# dip.net
KiCad netlist of a schematic drawn in EAGLE
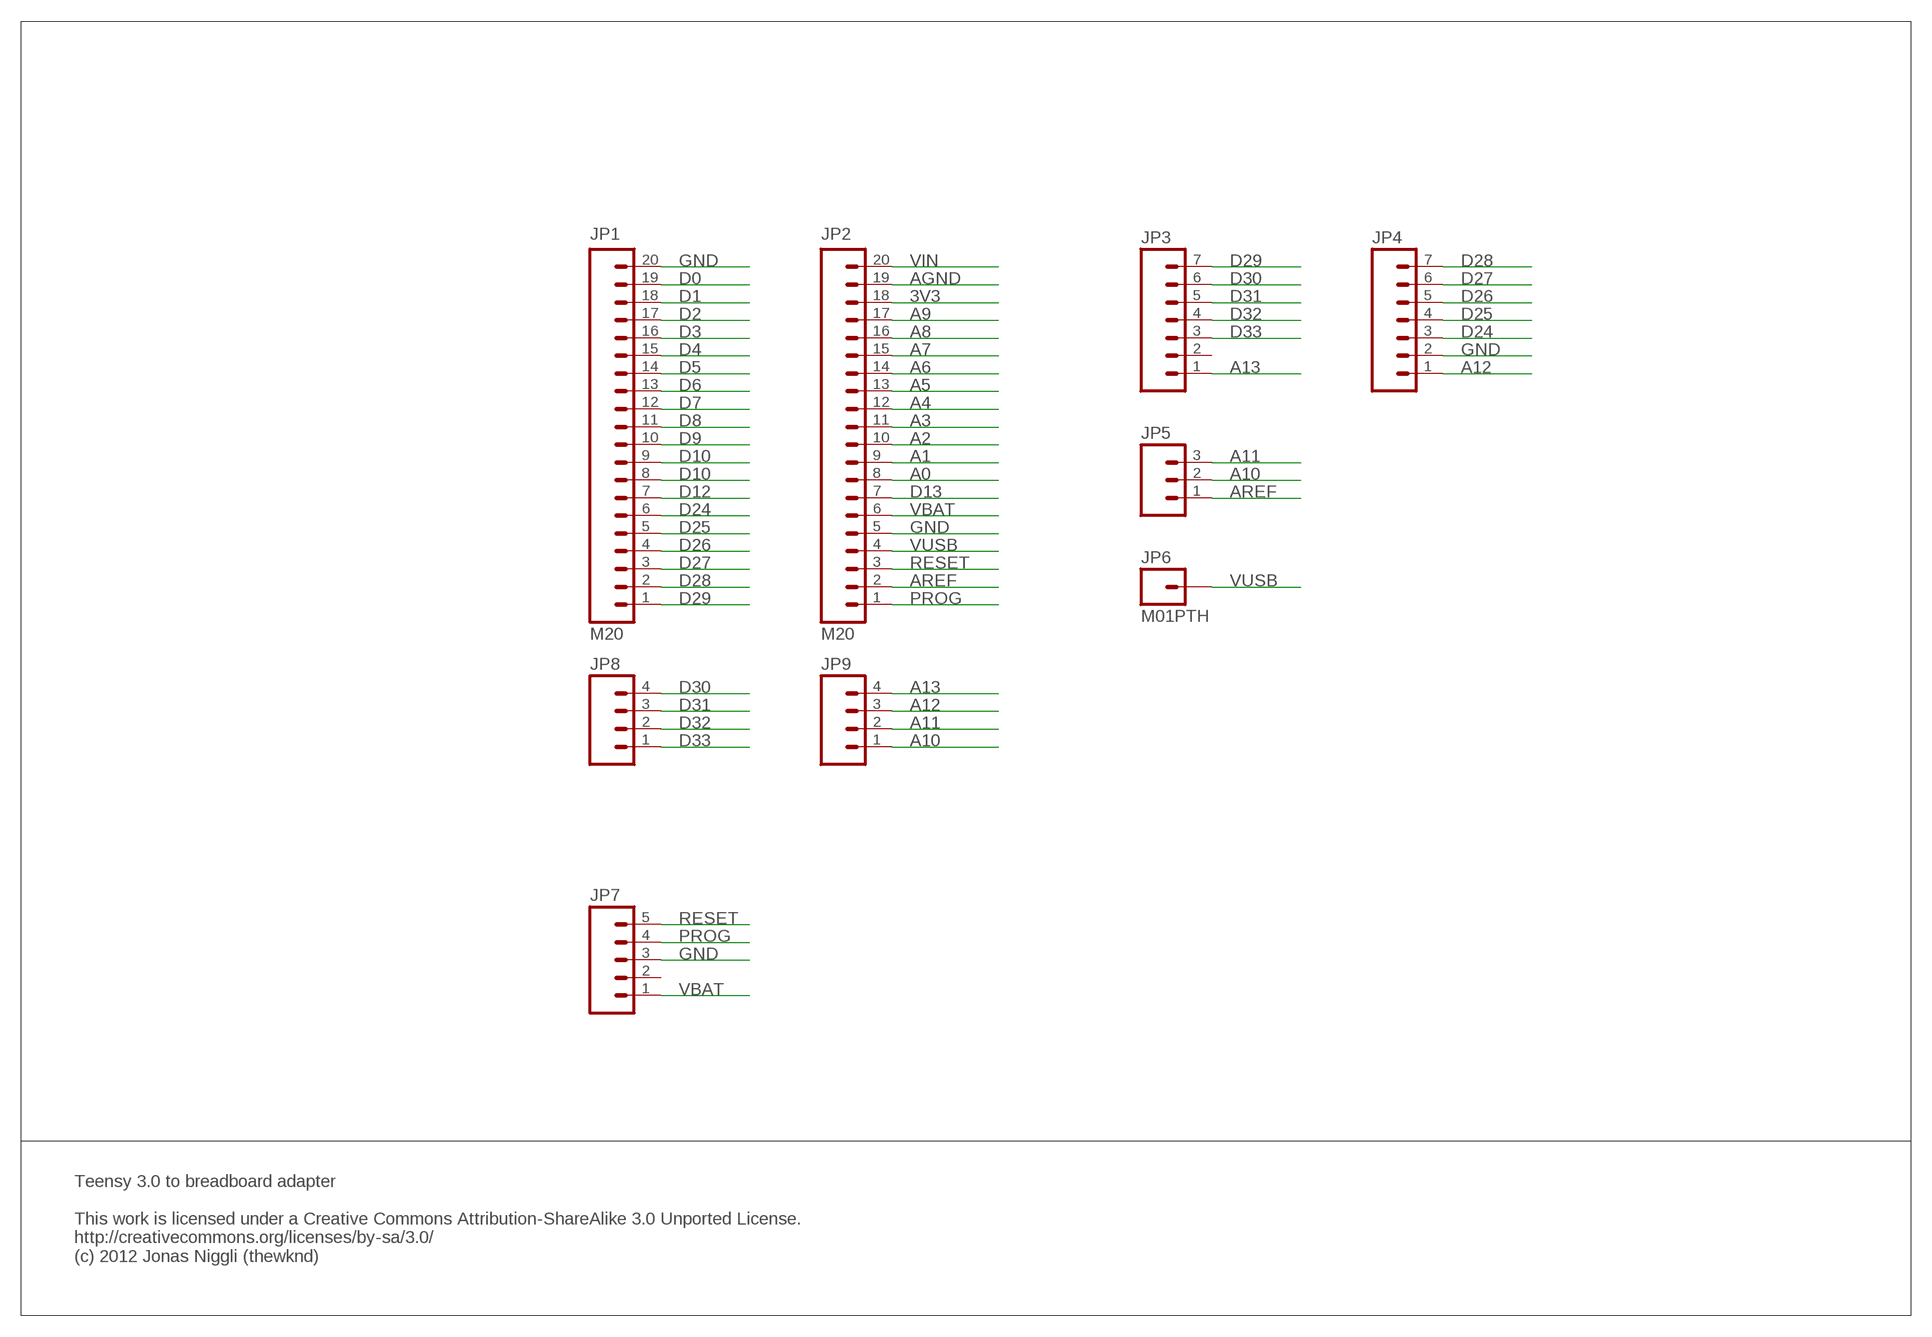
[diagram p0: schematic, sheet 1]

(export (version "E")
  (design (tool "Eeschema 10.0.6"))
  (components
    (comp (ref "JP1")
      (value "M20")
      (footprint "eagle-import:1X20")
      (libsource (lib "eagle-import") (part "M20"))
    )
    (comp (ref "JP2")
      (value "M20")
      (footprint "eagle-import:1X20")
      (libsource (lib "eagle-import") (part "M20"))
    )
    (comp (ref "JP3")
      (value "M07")
      (footprint "eagle-import:1X07")
      (libsource (lib "eagle-import") (part "M07"))
    )
    (comp (ref "JP4")
      (value "M07")
      (footprint "eagle-import:1X07")
      (libsource (lib "eagle-import") (part "M07"))
    )
    (comp (ref "JP5")
      (value "M03PTH")
      (footprint "eagle-import:1X03")
      (libsource (lib "eagle-import") (part "M03PTH"))
    )
    (comp (ref "JP6")
      (value "M01PTH")
      (footprint "eagle-import:1X01")
      (libsource (lib "eagle-import") (part "M01PTH"))
    )
    (comp (ref "JP7")
      (value "M05PTH")
      (footprint "eagle-import:1X05")
      (libsource (lib "eagle-import") (part "M05PTH"))
    )
    (comp (ref "JP8")
      (value "M04PTH")
      (footprint "eagle-import:1X04")
      (libsource (lib "eagle-import") (part "M04PTH"))
    )
    (comp (ref "JP9")
      (value "M04PTH")
      (footprint "eagle-import:1X04")
      (libsource (lib "eagle-import") (part "M04PTH"))
    )
  )
  (nets
    (net (code "1") (name "/3V3") (class "Default")
      (node (ref "JP2") (pin "18") (pinfunction "18_18") (pintype "passive"))
    )
    (net (code "2") (name "/A0") (class "Default")
      (node (ref "JP2") (pin "8") (pinfunction "8_8") (pintype "passive"))
    )
    (net (code "3") (name "/A1") (class "Default")
      (node (ref "JP2") (pin "9") (pinfunction "9_9") (pintype "passive"))
    )
    (net (code "4") (name "/A2") (class "Default")
      (node (ref "JP2") (pin "10") (pinfunction "10_10") (pintype "passive"))
    )
    (net (code "5") (name "/A3") (class "Default")
      (node (ref "JP2") (pin "11") (pinfunction "11_11") (pintype "passive"))
    )
    (net (code "6") (name "/A4") (class "Default")
      (node (ref "JP2") (pin "12") (pinfunction "12_12") (pintype "passive"))
    )
    (net (code "7") (name "/A5") (class "Default")
      (node (ref "JP2") (pin "13") (pinfunction "13_13") (pintype "passive"))
    )
    (net (code "8") (name "/A6") (class "Default")
      (node (ref "JP2") (pin "14") (pinfunction "14_14") (pintype "passive"))
    )
    (net (code "9") (name "/A7") (class "Default")
      (node (ref "JP2") (pin "15") (pinfunction "15_15") (pintype "passive"))
    )
    (net (code "10") (name "/A8") (class "Default")
      (node (ref "JP2") (pin "16") (pinfunction "16_16") (pintype "passive"))
    )
    (net (code "11") (name "/A9") (class "Default")
      (node (ref "JP2") (pin "17") (pinfunction "17_17") (pintype "passive"))
    )
    (net (code "12") (name "/A10") (class "Default")
      (node (ref "JP5") (pin "2") (pinfunction "2_2") (pintype "passive"))
      (node (ref "JP9") (pin "1") (pinfunction "1_1") (pintype "passive"))
    )
    (net (code "13") (name "/A11") (class "Default")
      (node (ref "JP5") (pin "3") (pinfunction "3_3") (pintype "passive"))
      (node (ref "JP9") (pin "2") (pinfunction "2_2") (pintype "passive"))
    )
    (net (code "14") (name "/A12") (class "Default")
      (node (ref "JP4") (pin "1") (pinfunction "1_1") (pintype "passive"))
      (node (ref "JP9") (pin "3") (pinfunction "3_3") (pintype "passive"))
    )
    (net (code "15") (name "/A13") (class "Default")
      (node (ref "JP3") (pin "1") (pinfunction "1_1") (pintype "passive"))
      (node (ref "JP9") (pin "4") (pinfunction "4_4") (pintype "passive"))
    )
    (net (code "16") (name "/AGND") (class "Default")
      (node (ref "JP2") (pin "19") (pinfunction "19_19") (pintype "passive"))
    )
    (net (code "17") (name "/AREF") (class "Default")
      (node (ref "JP2") (pin "2") (pinfunction "2_2") (pintype "passive"))
      (node (ref "JP5") (pin "1") (pinfunction "1_1") (pintype "passive"))
    )
    (net (code "18") (name "/D0") (class "Default")
      (node (ref "JP1") (pin "19") (pinfunction "19_19") (pintype "passive"))
    )
    (net (code "19") (name "/D1") (class "Default")
      (node (ref "JP1") (pin "18") (pinfunction "18_18") (pintype "passive"))
    )
    (net (code "20") (name "/D2") (class "Default")
      (node (ref "JP1") (pin "17") (pinfunction "17_17") (pintype "passive"))
    )
    (net (code "21") (name "/D3") (class "Default")
      (node (ref "JP1") (pin "16") (pinfunction "16_16") (pintype "passive"))
    )
    (net (code "22") (name "/D4") (class "Default")
      (node (ref "JP1") (pin "15") (pinfunction "15_15") (pintype "passive"))
    )
    (net (code "23") (name "/D5") (class "Default")
      (node (ref "JP1") (pin "14") (pinfunction "14_14") (pintype "passive"))
    )
    (net (code "24") (name "/D6") (class "Default")
      (node (ref "JP1") (pin "13") (pinfunction "13_13") (pintype "passive"))
    )
    (net (code "25") (name "/D7") (class "Default")
      (node (ref "JP1") (pin "12") (pinfunction "12_12") (pintype "passive"))
    )
    (net (code "26") (name "/D8") (class "Default")
      (node (ref "JP1") (pin "11") (pinfunction "11_11") (pintype "passive"))
    )
    (net (code "27") (name "/D9") (class "Default")
      (node (ref "JP1") (pin "10") (pinfunction "10_10") (pintype "passive"))
    )
    (net (code "28") (name "/D10") (class "Default")
      (node (ref "JP1") (pin "9") (pinfunction "9_9") (pintype "passive"))
    )
    (net (code "29") (name "/D12") (class "Default")
      (node (ref "JP1") (pin "7") (pinfunction "7_7") (pintype "passive"))
    )
    (net (code "30") (name "/D13") (class "Default")
      (node (ref "JP2") (pin "7") (pinfunction "7_7") (pintype "passive"))
    )
    (net (code "31") (name "/D24") (class "Default")
      (node (ref "JP1") (pin "6") (pinfunction "6_6") (pintype "passive"))
      (node (ref "JP4") (pin "3") (pinfunction "3_3") (pintype "passive"))
    )
    (net (code "32") (name "/D25") (class "Default")
      (node (ref "JP1") (pin "5") (pinfunction "5_5") (pintype "passive"))
      (node (ref "JP4") (pin "4") (pinfunction "4_4") (pintype "passive"))
    )
    (net (code "33") (name "/D26") (class "Default")
      (node (ref "JP1") (pin "4") (pinfunction "4_4") (pintype "passive"))
      (node (ref "JP4") (pin "5") (pinfunction "5_5") (pintype "passive"))
    )
    (net (code "34") (name "/D27") (class "Default")
      (node (ref "JP1") (pin "3") (pinfunction "3_3") (pintype "passive"))
      (node (ref "JP4") (pin "6") (pinfunction "6_6") (pintype "passive"))
    )
    (net (code "35") (name "/D28") (class "Default")
      (node (ref "JP1") (pin "2") (pinfunction "2_2") (pintype "passive"))
      (node (ref "JP4") (pin "7") (pinfunction "7_7") (pintype "passive"))
    )
    (net (code "36") (name "/D29") (class "Default")
      (node (ref "JP1") (pin "1") (pinfunction "1_1") (pintype "passive"))
      (node (ref "JP3") (pin "7") (pinfunction "7_7") (pintype "passive"))
    )
    (net (code "37") (name "/D30") (class "Default")
      (node (ref "JP3") (pin "6") (pinfunction "6_6") (pintype "passive"))
      (node (ref "JP8") (pin "4") (pinfunction "4_4") (pintype "passive"))
    )
    (net (code "38") (name "/D31") (class "Default")
      (node (ref "JP3") (pin "5") (pinfunction "5_5") (pintype "passive"))
      (node (ref "JP8") (pin "3") (pinfunction "3_3") (pintype "passive"))
    )
    (net (code "39") (name "/D32") (class "Default")
      (node (ref "JP3") (pin "4") (pinfunction "4_4") (pintype "passive"))
      (node (ref "JP8") (pin "2") (pinfunction "2_2") (pintype "passive"))
    )
    (net (code "40") (name "/D33") (class "Default")
      (node (ref "JP3") (pin "3") (pinfunction "3_3") (pintype "passive"))
      (node (ref "JP8") (pin "1") (pinfunction "1_1") (pintype "passive"))
    )
    (net (code "41") (name "/GND") (class "Default")
      (node (ref "JP1") (pin "20") (pinfunction "20_20") (pintype "passive"))
      (node (ref "JP2") (pin "5") (pinfunction "5_5") (pintype "passive"))
      (node (ref "JP4") (pin "2") (pinfunction "2_2") (pintype "passive"))
      (node (ref "JP7") (pin "3") (pinfunction "3_3") (pintype "passive"))
    )
    (net (code "42") (name "/PROG") (class "Default")
      (node (ref "JP2") (pin "1") (pinfunction "1_1") (pintype "passive"))
      (node (ref "JP7") (pin "4") (pinfunction "4_4") (pintype "passive"))
    )
    (net (code "43") (name "/RESET") (class "Default")
      (node (ref "JP2") (pin "3") (pinfunction "3_3") (pintype "passive"))
      (node (ref "JP7") (pin "5") (pinfunction "5_5") (pintype "passive"))
    )
    (net (code "44") (name "/VBAT") (class "Default")
      (node (ref "JP2") (pin "6") (pinfunction "6_6") (pintype "passive"))
      (node (ref "JP7") (pin "1") (pinfunction "1_1") (pintype "passive"))
    )
    (net (code "45") (name "/VIN") (class "Default")
      (node (ref "JP2") (pin "20") (pinfunction "20_20") (pintype "passive"))
    )
    (net (code "46") (name "/VUSB") (class "Default")
      (node (ref "JP2") (pin "4") (pinfunction "4_4") (pintype "passive"))
      (node (ref "JP6") (pin "1") (pinfunction "1_1") (pintype "passive"))
    )
    (net (code "47") (name "unconnected-(JP1-Pad8)") (class "Default")
      (node (ref "JP1") (pin "8") (pinfunction "8_8") (pintype "passive"))
    )
    (net (code "48") (name "unconnected-(JP3-Pad2)") (class "Default")
      (node (ref "JP3") (pin "2") (pinfunction "2_2") (pintype "passive"))
    )
    (net (code "49") (name "unconnected-(JP7-Pad2)") (class "Default")
      (node (ref "JP7") (pin "2") (pinfunction "2_2") (pintype "passive"))
    )
  )
)
